# Groupe3_Hermant-Bohyn-Almasy-Ponjee.net
KiCad netlist of a schematic drawn in EAGLE
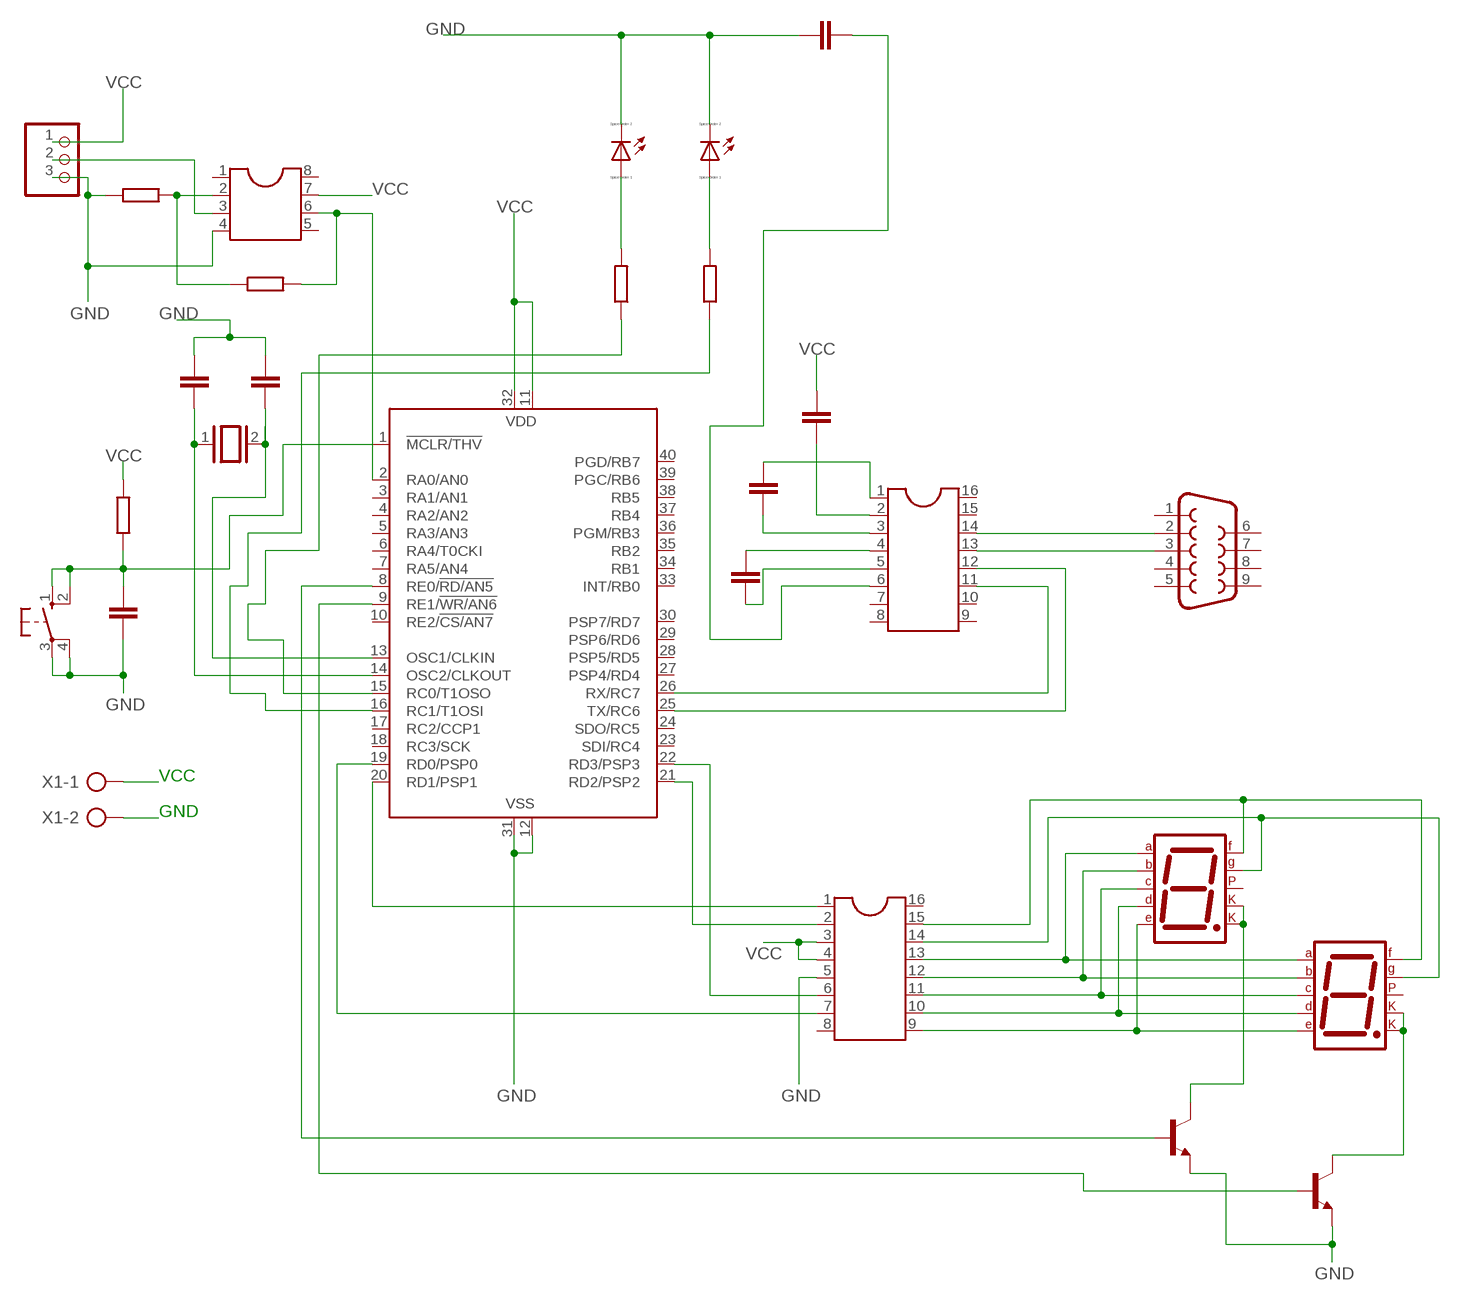
[diagram p0: schematic, sheet 1]

(export (version "E")
  (design (tool "Eeschema 10.0.6"))
  (components
    (comp (ref "4511")
      (value "DIL16")
      (footprint "eagle-import:DIL16")
      (libsource (lib "eagle-import") (part "DIL16"))
    )
    (comp (ref "AMPLIOP")
      (value "DIL8")
      (footprint "eagle-import:DIL08")
      (libsource (lib "eagle-import") (part "DIL8"))
    )
    (comp (ref "C1")
      (value "15pF")
      (footprint "eagle-import:C025-050X050")
      (libsource (lib "eagle-import") (part "C-EU025-050X050"))
    )
    (comp (ref "C2")
      (value "15pF")
      (footprint "eagle-import:C025-050X050")
      (libsource (lib "eagle-import") (part "C-EU025-050X050"))
    )
    (comp (ref "C3")
      (value "1uF")
      (footprint "eagle-import:C025-050X050")
      (libsource (lib "eagle-import") (part "C-EU025-050X050"))
    )
    (comp (ref "C4")
      (value "10uF")
      (footprint "eagle-import:C025-050X050")
      (libsource (lib "eagle-import") (part "C-EU025-050X050"))
    )
    (comp (ref "C5")
      (value "10uF")
      (footprint "eagle-import:C025-050X050")
      (libsource (lib "eagle-import") (part "C-EU025-050X050"))
    )
    (comp (ref "C7")
      (value "100u")
      (footprint "eagle-import:C025-050X050")
      (libsource (lib "eagle-import") (part "C-EU025-050X050"))
    )
    (comp (ref "C61")
      (value "10uF")
      (footprint "eagle-import:C025-050X050")
      (libsource (lib "eagle-import") (part "C-EU025-050X050"))
    )
    (comp (ref "D1")
      (value "7SEG-CK")
      (footprint "eagle-import:7SEG-13")
      (libsource (lib "eagle-import") (part "7SEG-CK"))
    )
    (comp (ref "D2")
      (value "7SEG-CK")
      (footprint "eagle-import:7SEG-13")
      (libsource (lib "eagle-import") (part "7SEG-CK"))
    )
    (comp (ref "LED1")
      (value "LED_ELD260")
      (footprint "eagle-import:LED_LD260")
      (libsource (lib "eagle-import") (part "LED_ELD260"))
    )
    (comp (ref "LED2")
      (value "LED_ELD260")
      (footprint "eagle-import:LED_LD260")
      (libsource (lib "eagle-import") (part "LED_ELD260"))
    )
    (comp (ref "LM35")
      (value "PINHD-1X3")
      (footprint "eagle-import:1X03")
      (libsource (lib "eagle-import") (part "PINHD-1X3"))
    )
    (comp (ref "MAX232")
      (value "DIL16")
      (footprint "eagle-import:DIL16")
      (libsource (lib "eagle-import") (part "DIL16"))
    )
    (comp (ref "P1/COMPIM")
      (value "F09V")
      (footprint "eagle-import:F09V")
      (libsource (lib "eagle-import") (part "F09V"))
    )
    (comp (ref "Q1")
      (value "2N2222")
      (footprint "eagle-import:TO18")
      (libsource (lib "eagle-import") (part "2N2222"))
    )
    (comp (ref "Q2")
      (value "2N2222")
      (footprint "eagle-import:TO18")
      (libsource (lib "eagle-import") (part "2N2222"))
    )
    (comp (ref "R1")
      (value "10k")
      (footprint "eagle-import:0204_7")
      (libsource (lib "eagle-import") (part "R-EU_0204/7"))
    )
    (comp (ref "R2")
      (value "4k")
      (footprint "eagle-import:0204_7")
      (libsource (lib "eagle-import") (part "R-EU_0204/7"))
    )
    (comp (ref "R3")
      (value "1k")
      (footprint "eagle-import:0204_7")
      (libsource (lib "eagle-import") (part "R-EU_0204/7"))
    )
    (comp (ref "R4")
      (value "280")
      (footprint "eagle-import:0204_7")
      (libsource (lib "eagle-import") (part "R-EU_0204/7"))
    )
    (comp (ref "R5")
      (value "280")
      (footprint "eagle-import:0204_7")
      (libsource (lib "eagle-import") (part "R-EU_0204/7"))
    )
    (comp (ref "S1")
      (value "10-XX")
      (footprint "eagle-import:B3F-10XX")
      (fields (field (name "MPN") "B3F-1000"))
      (libsource (lib "eagle-import") (part "10-XX"))
    )
    (comp (ref "U1")
      (value "PIC16F877P")
      (footprint "eagle-import:DIL40")
      (fields (field (name "MF") "MICROCHIP") (field (name "MPN") "PIC16F877-04/P"))
      (libsource (lib "eagle-import") (part "PIC16F87P7"))
    )
    (comp (ref "X1")
      (value "AK300/2")
      (footprint "eagle-import:AK300_2")
      (libsource (lib "eagle-import") (part "AK300/2"))
    )
    (comp (ref "X11")
      (value "XTAL/S")
      (footprint "eagle-import:QS")
      (libsource (lib "eagle-import") (part "XTAL/S"))
    )
  )
  (nets
    (net (code "1") (name "/GND") (class "Default")
      (node (ref "4511") (pin "5") (pinfunction "5_5") (pintype "passive"))
      (node (ref "AMPLIOP") (pin "4") (pinfunction "4_4") (pintype "passive"))
      (node (ref "C1") (pin "1") (pinfunction "1_1") (pintype "passive"))
      (node (ref "C2") (pin "1") (pinfunction "1_1") (pintype "passive"))
      (node (ref "C3") (pin "1") (pinfunction "1_1") (pintype "passive"))
      (node (ref "C61") (pin "2") (pinfunction "2_2") (pintype "passive"))
      (node (ref "LED1") (pin "K") (pinfunction "C_K") (pintype "passive"))
      (node (ref "LED2") (pin "K") (pinfunction "C_K") (pintype "passive"))
      (node (ref "LM35") (pin "3") (pinfunction "3_3") (pintype "passive"))
      (node (ref "Q1") (pin "1") (pinfunction "E_1") (pintype "passive"))
      (node (ref "Q2") (pin "1") (pinfunction "E_1") (pintype "passive"))
      (node (ref "R2") (pin "1") (pinfunction "1_1") (pintype "passive"))
      (node (ref "S1") (pin "3") (pinfunction "P_3") (pintype "passive"))
      (node (ref "S1") (pin "4") (pinfunction "P1_4") (pintype "passive"))
      (node (ref "U1") (pin "12") (pinfunction "VSS_12") (pintype "power_in"))
      (node (ref "U1") (pin "31") (pinfunction "VSS_31") (pintype "power_in"))
      (node (ref "X1") (pin "2") (pinfunction "KL_2") (pintype "passive"))
    )
    (net (code "2") (name "/VCC") (class "Default")
      (node (ref "4511") (pin "3") (pinfunction "3_3") (pintype "passive"))
      (node (ref "4511") (pin "4") (pinfunction "4_4") (pintype "passive"))
      (node (ref "AMPLIOP") (pin "7") (pinfunction "7_7") (pintype "passive"))
      (node (ref "C7") (pin "2") (pinfunction "2_2") (pintype "passive"))
      (node (ref "LM35") (pin "1") (pinfunction "1_1") (pintype "passive"))
      (node (ref "R1") (pin "2") (pinfunction "2_2") (pintype "passive"))
      (node (ref "U1") (pin "11") (pinfunction "VDD_11") (pintype "power_in"))
      (node (ref "U1") (pin "32") (pinfunction "VDD_32") (pintype "power_in"))
      (node (ref "X1") (pin "1") (pinfunction "KL_1") (pintype "passive"))
    )
    (net (code "3") (name "Net-(AMPLIOP-Pad2)") (class "Default")
      (node (ref "AMPLIOP") (pin "2") (pinfunction "2_2") (pintype "passive"))
      (node (ref "R2") (pin "2") (pinfunction "2_2") (pintype "passive"))
      (node (ref "R3") (pin "1") (pinfunction "1_1") (pintype "passive"))
    )
    (net (code "4") (name "Net-(AMPLIOP-Pad3)") (class "Default")
      (node (ref "AMPLIOP") (pin "3") (pinfunction "3_3") (pintype "passive"))
      (node (ref "LM35") (pin "2") (pinfunction "2_2") (pintype "passive"))
    )
    (net (code "5") (name "Net-(C4-Pad1)") (class "Default")
      (node (ref "C4") (pin "1") (pinfunction "1_1") (pintype "passive"))
      (node (ref "MAX232") (pin "3") (pinfunction "3_3") (pintype "passive"))
    )
    (net (code "6") (name "Net-(C4-Pad2)") (class "Default")
      (node (ref "C4") (pin "2") (pinfunction "2_2") (pintype "passive"))
      (node (ref "MAX232") (pin "1") (pinfunction "1_1") (pintype "passive"))
    )
    (net (code "7") (name "Net-(C5-Pad1)") (class "Default")
      (node (ref "C5") (pin "1") (pinfunction "1_1") (pintype "passive"))
      (node (ref "MAX232") (pin "5") (pinfunction "5_5") (pintype "passive"))
    )
    (net (code "8") (name "Net-(C5-Pad2)") (class "Default")
      (node (ref "C5") (pin "2") (pinfunction "2_2") (pintype "passive"))
      (node (ref "MAX232") (pin "4") (pinfunction "4_4") (pintype "passive"))
    )
    (net (code "9") (name "Net-(C7-Pad1)") (class "Default")
      (node (ref "C7") (pin "1") (pinfunction "1_1") (pintype "passive"))
      (node (ref "MAX232") (pin "2") (pinfunction "2_2") (pintype "passive"))
    )
    (net (code "10") (name "Net-(C61-Pad1)") (class "Default")
      (node (ref "C61") (pin "1") (pinfunction "1_1") (pintype "passive"))
      (node (ref "MAX232") (pin "6") (pinfunction "6_6") (pintype "passive"))
    )
    (net (code "11") (name "Net-(D1-A)") (class "Default")
      (node (ref "4511") (pin "13") (pinfunction "13_13") (pintype "passive"))
      (node (ref "D1") (pin "7") (pinfunction "A_7") (pintype "passive"))
      (node (ref "D2") (pin "7") (pinfunction "A_7") (pintype "passive"))
    )
    (net (code "12") (name "Net-(D1-B)") (class "Default")
      (node (ref "4511") (pin "12") (pinfunction "12_12") (pintype "passive"))
      (node (ref "D1") (pin "6") (pinfunction "B_6") (pintype "passive"))
      (node (ref "D2") (pin "6") (pinfunction "B_6") (pintype "passive"))
    )
    (net (code "13") (name "Net-(D1-C)") (class "Default")
      (node (ref "4511") (pin "11") (pinfunction "11_11") (pintype "passive"))
      (node (ref "D1") (pin "4") (pinfunction "C_4") (pintype "passive"))
      (node (ref "D2") (pin "4") (pinfunction "C_4") (pintype "passive"))
    )
    (net (code "14") (name "Net-(D1-CK1)") (class "Default")
      (node (ref "D1") (pin "3") (pinfunction "CK1_3") (pintype "passive"))
      (node (ref "D1") (pin "8") (pinfunction "CK2_8") (pintype "passive"))
      (node (ref "Q1") (pin "3") (pinfunction "C_3") (pintype "passive"))
    )
    (net (code "15") (name "Net-(D1-D)") (class "Default")
      (node (ref "4511") (pin "10") (pinfunction "10_10") (pintype "passive"))
      (node (ref "D1") (pin "2") (pinfunction "D_2") (pintype "passive"))
      (node (ref "D2") (pin "2") (pinfunction "D_2") (pintype "passive"))
    )
    (net (code "16") (name "Net-(D1-E)") (class "Default")
      (node (ref "4511") (pin "9") (pinfunction "9_9") (pintype "passive"))
      (node (ref "D1") (pin "1") (pinfunction "E_1") (pintype "passive"))
      (node (ref "D2") (pin "1") (pinfunction "E_1") (pintype "passive"))
    )
    (net (code "17") (name "Net-(D1-F)") (class "Default")
      (node (ref "4511") (pin "15") (pinfunction "15_15") (pintype "passive"))
      (node (ref "D1") (pin "9") (pinfunction "F_9") (pintype "passive"))
      (node (ref "D2") (pin "9") (pinfunction "F_9") (pintype "passive"))
    )
    (net (code "18") (name "Net-(D1-G)") (class "Default")
      (node (ref "4511") (pin "14") (pinfunction "14_14") (pintype "passive"))
      (node (ref "D1") (pin "10") (pinfunction "G_10") (pintype "passive"))
      (node (ref "D2") (pin "10") (pinfunction "G_10") (pintype "passive"))
    )
    (net (code "19") (name "Net-(D2-CK1)") (class "Default")
      (node (ref "D2") (pin "3") (pinfunction "CK1_3") (pintype "passive"))
      (node (ref "D2") (pin "8") (pinfunction "CK2_8") (pintype "passive"))
      (node (ref "Q2") (pin "3") (pinfunction "C_3") (pintype "passive"))
    )
    (net (code "20") (name "Net-(LED1-PadA)") (class "Default")
      (node (ref "LED1") (pin "A") (pinfunction "A_A") (pintype "passive"))
      (node (ref "R4") (pin "2") (pinfunction "2_2") (pintype "passive"))
    )
    (net (code "21") (name "Net-(LED2-PadA)") (class "Default")
      (node (ref "LED2") (pin "A") (pinfunction "A_A") (pintype "passive"))
      (node (ref "R5") (pin "2") (pinfunction "2_2") (pintype "passive"))
    )
    (net (code "22") (name "Net-(MAX232-Pad13)") (class "Default")
      (node (ref "MAX232") (pin "13") (pinfunction "13_13") (pintype "passive"))
      (node (ref "P1/COMPIM") (pin "3") (pinfunction "3_3") (pintype "passive"))
    )
    (net (code "23") (name "Net-(MAX232-Pad14)") (class "Default")
      (node (ref "MAX232") (pin "14") (pinfunction "14_14") (pintype "passive"))
      (node (ref "P1/COMPIM") (pin "2") (pinfunction "2_2") (pintype "passive"))
    )
    (net (code "24") (name "Net-(Q1-B)") (class "Default")
      (node (ref "Q1") (pin "2") (pinfunction "B_2") (pintype "passive"))
      (node (ref "U1") (pin "8") (pinfunction "RE0/~{RD/AN5}_8") (pintype "bidirectional"))
    )
    (net (code "25") (name "Net-(Q2-B)") (class "Default")
      (node (ref "Q2") (pin "2") (pinfunction "B_2") (pintype "passive"))
      (node (ref "U1") (pin "9") (pinfunction "RE1/~{WR/AN6}_9") (pintype "bidirectional"))
    )
    (net (code "26") (name "Net-(S1-S)") (class "Default")
      (node (ref "C3") (pin "2") (pinfunction "2_2") (pintype "passive"))
      (node (ref "R1") (pin "1") (pinfunction "1_1") (pintype "passive"))
      (node (ref "S1") (pin "1") (pinfunction "S_1") (pintype "passive"))
      (node (ref "S1") (pin "2") (pinfunction "S1_2") (pintype "passive"))
      (node (ref "U1") (pin "1") (pinfunction "~{MCLR/THV}_1") (pintype "input"))
    )
    (net (code "27") (name "Net-(U1-OSC1{slash}CLKIN)") (class "Default")
      (node (ref "C1") (pin "2") (pinfunction "2_2") (pintype "passive"))
      (node (ref "U1") (pin "13") (pinfunction "OSC1/CLKIN_13") (pintype "input"))
      (node (ref "X11") (pin "2") (pinfunction "2_2") (pintype "passive"))
    )
    (net (code "28") (name "Net-(U1-OSC2{slash}CLKOUT)") (class "Default")
      (node (ref "C2") (pin "2") (pinfunction "2_2") (pintype "passive"))
      (node (ref "U1") (pin "14") (pinfunction "OSC2/CLKOUT_14") (pintype "output"))
      (node (ref "X11") (pin "1") (pinfunction "1_1") (pintype "passive"))
    )
    (net (code "29") (name "Net-(U1-RA0{slash}AN0)") (class "Default")
      (node (ref "AMPLIOP") (pin "6") (pinfunction "6_6") (pintype "passive"))
      (node (ref "R3") (pin "2") (pinfunction "2_2") (pintype "passive"))
      (node (ref "U1") (pin "2") (pinfunction "RA0/AN0_2") (pintype "bidirectional"))
    )
    (net (code "30") (name "Net-(U1-RC0{slash}T1OSO)") (class "Default")
      (node (ref "R4") (pin "1") (pinfunction "1_1") (pintype "passive"))
      (node (ref "U1") (pin "15") (pinfunction "RC0/T1OSO_15") (pintype "bidirectional"))
    )
    (net (code "31") (name "Net-(U1-RC1{slash}T1OSI)") (class "Default")
      (node (ref "R5") (pin "1") (pinfunction "1_1") (pintype "passive"))
      (node (ref "U1") (pin "16") (pinfunction "RC1/T1OSI_16") (pintype "bidirectional"))
    )
    (net (code "32") (name "Net-(U1-RD0{slash}PSP0)") (class "Default")
      (node (ref "4511") (pin "7") (pinfunction "7_7") (pintype "passive"))
      (node (ref "U1") (pin "19") (pinfunction "RD0/PSP0_19") (pintype "bidirectional"))
    )
    (net (code "33") (name "Net-(U1-RD1{slash}PSP1)") (class "Default")
      (node (ref "4511") (pin "1") (pinfunction "1_1") (pintype "passive"))
      (node (ref "U1") (pin "20") (pinfunction "RD1/PSP1_20") (pintype "bidirectional"))
    )
    (net (code "34") (name "Net-(U1-RD2{slash}PSP2)") (class "Default")
      (node (ref "4511") (pin "2") (pinfunction "2_2") (pintype "passive"))
      (node (ref "U1") (pin "21") (pinfunction "RD2/PSP2_21") (pintype "bidirectional"))
    )
    (net (code "35") (name "Net-(U1-RD3{slash}PSP3)") (class "Default")
      (node (ref "4511") (pin "6") (pinfunction "6_6") (pintype "passive"))
      (node (ref "U1") (pin "22") (pinfunction "RD3/PSP3_22") (pintype "bidirectional"))
    )
    (net (code "36") (name "Net-(U1-RX{slash}RC7)") (class "Default")
      (node (ref "MAX232") (pin "11") (pinfunction "11_11") (pintype "passive"))
      (node (ref "U1") (pin "26") (pinfunction "RX/RC7_26") (pintype "bidirectional"))
    )
    (net (code "37") (name "Net-(U1-TX{slash}RC6)") (class "Default")
      (node (ref "MAX232") (pin "12") (pinfunction "12_12") (pintype "passive"))
      (node (ref "U1") (pin "25") (pinfunction "TX/RC6_25") (pintype "bidirectional"))
    )
    (net (code "38") (name "unconnected-(4511-Pad8)") (class "Default")
      (node (ref "4511") (pin "8") (pinfunction "8_8") (pintype "passive"))
    )
    (net (code "39") (name "unconnected-(4511-Pad16)") (class "Default")
      (node (ref "4511") (pin "16") (pinfunction "16_16") (pintype "passive"))
    )
    (net (code "40") (name "unconnected-(AMPLIOP-Pad1)") (class "Default")
      (node (ref "AMPLIOP") (pin "1") (pinfunction "1_1") (pintype "passive"))
    )
    (net (code "41") (name "unconnected-(AMPLIOP-Pad5)") (class "Default")
      (node (ref "AMPLIOP") (pin "5") (pinfunction "5_5") (pintype "passive"))
    )
    (net (code "42") (name "unconnected-(AMPLIOP-Pad8)") (class "Default")
      (node (ref "AMPLIOP") (pin "8") (pinfunction "8_8") (pintype "passive"))
    )
    (net (code "43") (name "unconnected-(D1-DP-Pad5)") (class "Default")
      (node (ref "D1") (pin "5") (pinfunction "DP_5") (pintype "passive"))
    )
    (net (code "44") (name "unconnected-(D2-DP-Pad5)") (class "Default")
      (node (ref "D2") (pin "5") (pinfunction "DP_5") (pintype "passive"))
    )
    (net (code "45") (name "unconnected-(MAX232-Pad7)") (class "Default")
      (node (ref "MAX232") (pin "7") (pinfunction "7_7") (pintype "passive"))
    )
    (net (code "46") (name "unconnected-(MAX232-Pad8)") (class "Default")
      (node (ref "MAX232") (pin "8") (pinfunction "8_8") (pintype "passive"))
    )
    (net (code "47") (name "unconnected-(MAX232-Pad9)") (class "Default")
      (node (ref "MAX232") (pin "9") (pinfunction "9_9") (pintype "passive"))
    )
    (net (code "48") (name "unconnected-(MAX232-Pad10)") (class "Default")
      (node (ref "MAX232") (pin "10") (pinfunction "10_10") (pintype "passive"))
    )
    (net (code "49") (name "unconnected-(MAX232-Pad15)") (class "Default")
      (node (ref "MAX232") (pin "15") (pinfunction "15_15") (pintype "passive"))
    )
    (net (code "50") (name "unconnected-(MAX232-Pad16)") (class "Default")
      (node (ref "MAX232") (pin "16") (pinfunction "16_16") (pintype "passive"))
    )
    (net (code "51") (name "unconnected-(P1/COMPIM-Pad1)") (class "Default")
      (node (ref "P1/COMPIM") (pin "1") (pinfunction "1_1") (pintype "passive"))
    )
    (net (code "52") (name "unconnected-(P1/COMPIM-Pad4)") (class "Default")
      (node (ref "P1/COMPIM") (pin "4") (pinfunction "4_4") (pintype "passive"))
    )
    (net (code "53") (name "unconnected-(P1/COMPIM-Pad5)") (class "Default")
      (node (ref "P1/COMPIM") (pin "5") (pinfunction "5_5") (pintype "passive"))
    )
    (net (code "54") (name "unconnected-(P1/COMPIM-Pad6)") (class "Default")
      (node (ref "P1/COMPIM") (pin "6") (pinfunction "6_6") (pintype "passive"))
    )
    (net (code "55") (name "unconnected-(P1/COMPIM-Pad7)") (class "Default")
      (node (ref "P1/COMPIM") (pin "7") (pinfunction "7_7") (pintype "passive"))
    )
    (net (code "56") (name "unconnected-(P1/COMPIM-Pad8)") (class "Default")
      (node (ref "P1/COMPIM") (pin "8") (pinfunction "8_8") (pintype "passive"))
    )
    (net (code "57") (name "unconnected-(P1/COMPIM-Pad9)") (class "Default")
      (node (ref "P1/COMPIM") (pin "9") (pinfunction "9_9") (pintype "passive"))
    )
    (net (code "58") (name "unconnected-(U1-INT{slash}RB0-Pad33)") (class "Default")
      (node (ref "U1") (pin "33") (pinfunction "INT/RB0_33") (pintype "bidirectional"))
    )
    (net (code "59") (name "unconnected-(U1-PGC{slash}RB6-Pad39)") (class "Default")
      (node (ref "U1") (pin "39") (pinfunction "PGC/RB6_39") (pintype "bidirectional"))
    )
    (net (code "60") (name "unconnected-(U1-PGD{slash}RB7-Pad40)") (class "Default")
      (node (ref "U1") (pin "40") (pinfunction "PGD/RB7_40") (pintype "bidirectional"))
    )
    (net (code "61") (name "unconnected-(U1-PGM{slash}RB3-Pad36)") (class "Default")
      (node (ref "U1") (pin "36") (pinfunction "PGM/RB3_36") (pintype "bidirectional"))
    )
    (net (code "62") (name "unconnected-(U1-PSP4{slash}RD4-Pad27)") (class "Default")
      (node (ref "U1") (pin "27") (pinfunction "PSP4/RD4_27") (pintype "bidirectional"))
    )
    (net (code "63") (name "unconnected-(U1-PSP5{slash}RD5-Pad28)") (class "Default")
      (node (ref "U1") (pin "28") (pinfunction "PSP5/RD5_28") (pintype "bidirectional"))
    )
    (net (code "64") (name "unconnected-(U1-PSP6{slash}RD6-Pad29)") (class "Default")
      (node (ref "U1") (pin "29") (pinfunction "PSP6/RD6_29") (pintype "bidirectional"))
    )
    (net (code "65") (name "unconnected-(U1-PSP7{slash}RD7-Pad30)") (class "Default")
      (node (ref "U1") (pin "30") (pinfunction "PSP7/RD7_30") (pintype "bidirectional"))
    )
    (net (code "66") (name "unconnected-(U1-RA1{slash}AN1-Pad3)") (class "Default")
      (node (ref "U1") (pin "3") (pinfunction "RA1/AN1_3") (pintype "bidirectional"))
    )
    (net (code "67") (name "unconnected-(U1-RA2{slash}AN2-Pad4)") (class "Default")
      (node (ref "U1") (pin "4") (pinfunction "RA2/AN2_4") (pintype "bidirectional"))
    )
    (net (code "68") (name "unconnected-(U1-RA3{slash}AN3-Pad5)") (class "Default")
      (node (ref "U1") (pin "5") (pinfunction "RA3/AN3_5") (pintype "bidirectional"))
    )
    (net (code "69") (name "unconnected-(U1-RA4{slash}T0CKI-Pad6)") (class "Default")
      (node (ref "U1") (pin "6") (pinfunction "RA4/T0CKI_6") (pintype "bidirectional"))
    )
    (net (code "70") (name "unconnected-(U1-RA5{slash}AN4-Pad7)") (class "Default")
      (node (ref "U1") (pin "7") (pinfunction "RA5/AN4_7") (pintype "bidirectional"))
    )
    (net (code "71") (name "unconnected-(U1-RB1-Pad34)") (class "Default")
      (node (ref "U1") (pin "34") (pinfunction "RB1_34") (pintype "bidirectional"))
    )
    (net (code "72") (name "unconnected-(U1-RB2-Pad35)") (class "Default")
      (node (ref "U1") (pin "35") (pinfunction "RB2_35") (pintype "bidirectional"))
    )
    (net (code "73") (name "unconnected-(U1-RB4-Pad37)") (class "Default")
      (node (ref "U1") (pin "37") (pinfunction "RB4_37") (pintype "bidirectional"))
    )
    (net (code "74") (name "unconnected-(U1-RB5-Pad38)") (class "Default")
      (node (ref "U1") (pin "38") (pinfunction "RB5_38") (pintype "bidirectional"))
    )
    (net (code "75") (name "unconnected-(U1-RC2{slash}CCP1-Pad17)") (class "Default")
      (node (ref "U1") (pin "17") (pinfunction "RC2/CCP1_17") (pintype "bidirectional"))
    )
    (net (code "76") (name "unconnected-(U1-RC3{slash}SCK-Pad18)") (class "Default")
      (node (ref "U1") (pin "18") (pinfunction "RC3/SCK_18") (pintype "bidirectional"))
    )
    (net (code "77") (name "unconnected-(U1-RE2{slash}~{CS{slash}AN7}-Pad10)") (class "Default")
      (node (ref "U1") (pin "10") (pinfunction "RE2/~{CS/AN7}_10") (pintype "bidirectional"))
    )
    (net (code "78") (name "unconnected-(U1-SDI{slash}RC4-Pad23)") (class "Default")
      (node (ref "U1") (pin "23") (pinfunction "SDI/RC4_23") (pintype "bidirectional"))
    )
    (net (code "79") (name "unconnected-(U1-SDO{slash}RC5-Pad24)") (class "Default")
      (node (ref "U1") (pin "24") (pinfunction "SDO/RC5_24") (pintype "bidirectional"))
    )
  )
)
